# ESPBaseboard.net
KiCad netlist of a schematic drawn in EAGLE
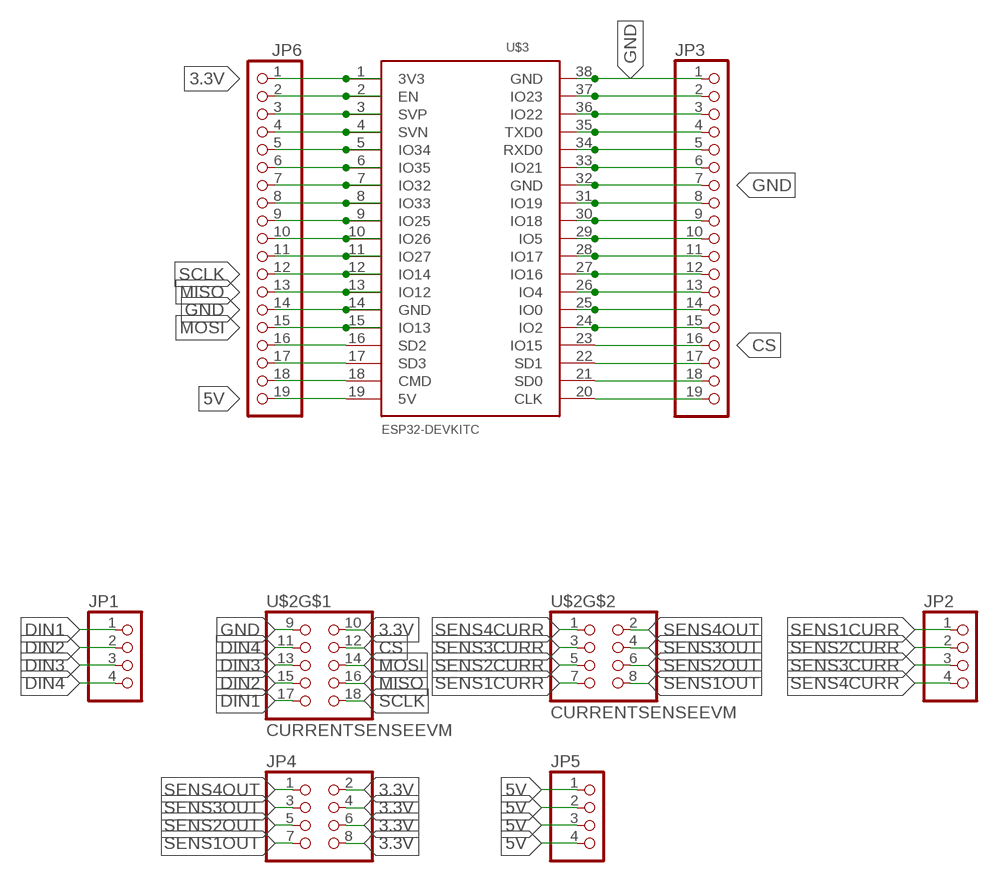
[diagram p0: schematic, sheet 1]

(export (version "E")
  (design (tool "Eeschema 10.0.6"))
  (components
    (comp (ref "JP1")
      (value "PINHD-1X4")
      (footprint "eagle-import:1X04")
      (libsource (lib "eagle-import") (part "PINHD-1X4"))
    )
    (comp (ref "JP2")
      (value "PINHD-1X4")
      (footprint "eagle-import:1X04")
      (libsource (lib "eagle-import") (part "PINHD-1X4"))
    )
    (comp (ref "JP3")
      (value "PINHD-1X19")
      (footprint "eagle-import:1X19")
      (libsource (lib "eagle-import") (part "PINHD-1X19"))
    )
    (comp (ref "JP4")
      (value "PINHD-2X4")
      (footprint "eagle-import:2X04")
      (libsource (lib "eagle-import") (part "PINHD-2X4"))
    )
    (comp (ref "JP5")
      (value "PINHD-1X4")
      (footprint "eagle-import:1X04")
      (libsource (lib "eagle-import") (part "PINHD-1X4"))
    )
    (comp (ref "JP6")
      (value "PINHD-1X19")
      (footprint "eagle-import:1X19")
      (libsource (lib "eagle-import") (part "PINHD-1X19"))
    )
    (comp (ref "U$2")
      (value "CURRENTSENSEEVM")
      (footprint "eagle-import:CURRENTSENSEEVM")
      (libsource (lib "eagle-import") (part "CURRENTSENSEEVM"))
    )
    (comp (ref "U$3")
      (value "ESP32DEVKITC")
      (footprint "eagle-import:ESP32-DEVKITC")
      (libsource (lib "eagle-import") (part "ESP32DEVKITC"))
    )
  )
  (nets
    (net (code "1") (name "3.3V") (class "Default")
      (node (ref "JP4") (pin "2") (pinfunction "2_2") (pintype "passive"))
      (node (ref "JP4") (pin "4") (pinfunction "4_4") (pintype "passive"))
      (node (ref "JP4") (pin "6") (pinfunction "6_6") (pintype "passive"))
      (node (ref "JP4") (pin "8") (pinfunction "8_8") (pintype "passive"))
      (node (ref "JP6") (pin "1") (pinfunction "1_1") (pintype "passive"))
      (node (ref "U$2") (pin "10") (pinfunction "2_10") (pintype "passive"))
      (node (ref "U$3") (pin "1") (pinfunction "3V3_1") (pintype "bidirectional"))
    )
    (net (code "2") (name "5V") (class "Default")
      (node (ref "JP5") (pin "1") (pinfunction "1_1") (pintype "passive"))
      (node (ref "JP5") (pin "2") (pinfunction "2_2") (pintype "passive"))
      (node (ref "JP5") (pin "3") (pinfunction "3_3") (pintype "passive"))
      (node (ref "JP5") (pin "4") (pinfunction "4_4") (pintype "passive"))
      (node (ref "JP6") (pin "19") (pinfunction "19_19") (pintype "passive"))
      (node (ref "U$3") (pin "19") (pinfunction "5V_19") (pintype "bidirectional"))
    )
    (net (code "3") (name "CS") (class "Default")
      (node (ref "JP3") (pin "10") (pinfunction "10_10") (pintype "passive"))
      (node (ref "JP3") (pin "16") (pinfunction "16_16") (pintype "passive"))
      (node (ref "U$2") (pin "12") (pinfunction "4_12") (pintype "passive"))
      (node (ref "U$3") (pin "23") (pinfunction "IO15_23") (pintype "bidirectional"))
      (node (ref "U$3") (pin "29") (pinfunction "IO5_29") (pintype "bidirectional"))
    )
    (net (code "4") (name "DIN1") (class "Default")
      (node (ref "JP1") (pin "1") (pinfunction "1_1") (pintype "passive"))
      (node (ref "U$2") (pin "17") (pinfunction "9_17") (pintype "passive"))
    )
    (net (code "5") (name "DIN2") (class "Default")
      (node (ref "JP1") (pin "2") (pinfunction "2_2") (pintype "passive"))
      (node (ref "U$2") (pin "15") (pinfunction "7_15") (pintype "passive"))
    )
    (net (code "6") (name "DIN3") (class "Default")
      (node (ref "JP1") (pin "3") (pinfunction "3_3") (pintype "passive"))
      (node (ref "U$2") (pin "13") (pinfunction "5_13") (pintype "passive"))
    )
    (net (code "7") (name "DIN4") (class "Default")
      (node (ref "JP1") (pin "4") (pinfunction "4_4") (pintype "passive"))
      (node (ref "U$2") (pin "11") (pinfunction "3_11") (pintype "passive"))
    )
    (net (code "8") (name "GND") (class "Default")
      (node (ref "JP3") (pin "1") (pinfunction "1_1") (pintype "passive"))
      (node (ref "JP3") (pin "7") (pinfunction "7_7") (pintype "passive"))
      (node (ref "JP6") (pin "14") (pinfunction "14_14") (pintype "passive"))
      (node (ref "U$2") (pin "9") (pinfunction "1_9") (pintype "passive"))
      (node (ref "U$3") (pin "14") (pinfunction "GND_14") (pintype "bidirectional"))
      (node (ref "U$3") (pin "32") (pinfunction "GND_32") (pintype "bidirectional"))
      (node (ref "U$3") (pin "38") (pinfunction "GND_38") (pintype "bidirectional"))
    )
    (net (code "9") (name "MISO") (class "Default")
      (node (ref "JP3") (pin "8") (pinfunction "8_8") (pintype "passive"))
      (node (ref "JP6") (pin "13") (pinfunction "13_13") (pintype "passive"))
      (node (ref "U$2") (pin "16") (pinfunction "8_16") (pintype "passive"))
      (node (ref "U$3") (pin "13") (pinfunction "IO12_13") (pintype "bidirectional"))
      (node (ref "U$3") (pin "31") (pinfunction "IO19_31") (pintype "bidirectional"))
    )
    (net (code "10") (name "MOSI") (class "Default")
      (node (ref "JP3") (pin "2") (pinfunction "2_2") (pintype "passive"))
      (node (ref "JP6") (pin "15") (pinfunction "15_15") (pintype "passive"))
      (node (ref "U$2") (pin "14") (pinfunction "6_14") (pintype "passive"))
      (node (ref "U$3") (pin "15") (pinfunction "IO13_15") (pintype "bidirectional"))
      (node (ref "U$3") (pin "37") (pinfunction "IO23_37") (pintype "bidirectional"))
    )
    (net (code "11") (name "Net-(U$3-CLK)") (class "Default")
      (node (ref "JP3") (pin "19") (pinfunction "19_19") (pintype "passive"))
      (node (ref "U$3") (pin "20") (pinfunction "CLK_20") (pintype "bidirectional"))
    )
    (net (code "12") (name "Net-(U$3-CMD)") (class "Default")
      (node (ref "JP6") (pin "18") (pinfunction "18_18") (pintype "passive"))
      (node (ref "U$3") (pin "18") (pinfunction "CMD_18") (pintype "bidirectional"))
    )
    (net (code "13") (name "Net-(U$3-EN)") (class "Default")
      (node (ref "JP6") (pin "2") (pinfunction "2_2") (pintype "passive"))
      (node (ref "U$3") (pin "2") (pinfunction "EN_2") (pintype "bidirectional"))
    )
    (net (code "14") (name "Net-(U$3-IO0)") (class "Default")
      (node (ref "JP3") (pin "14") (pinfunction "14_14") (pintype "passive"))
      (node (ref "U$3") (pin "25") (pinfunction "IO0_25") (pintype "bidirectional"))
    )
    (net (code "15") (name "Net-(U$3-IO2)") (class "Default")
      (node (ref "JP3") (pin "15") (pinfunction "15_15") (pintype "passive"))
      (node (ref "U$3") (pin "24") (pinfunction "IO2_24") (pintype "bidirectional"))
    )
    (net (code "16") (name "Net-(U$3-IO4)") (class "Default")
      (node (ref "JP3") (pin "13") (pinfunction "13_13") (pintype "passive"))
      (node (ref "U$3") (pin "26") (pinfunction "IO4_26") (pintype "bidirectional"))
    )
    (net (code "17") (name "Net-(U$3-IO16)") (class "Default")
      (node (ref "JP3") (pin "12") (pinfunction "12_12") (pintype "passive"))
      (node (ref "U$3") (pin "27") (pinfunction "IO16_27") (pintype "bidirectional"))
    )
    (net (code "18") (name "Net-(U$3-IO17)") (class "Default")
      (node (ref "JP3") (pin "11") (pinfunction "11_11") (pintype "passive"))
      (node (ref "U$3") (pin "28") (pinfunction "IO17_28") (pintype "bidirectional"))
    )
    (net (code "19") (name "Net-(U$3-IO21)") (class "Default")
      (node (ref "JP3") (pin "6") (pinfunction "6_6") (pintype "passive"))
      (node (ref "U$3") (pin "33") (pinfunction "IO21_33") (pintype "bidirectional"))
    )
    (net (code "20") (name "Net-(U$3-IO22)") (class "Default")
      (node (ref "JP3") (pin "3") (pinfunction "3_3") (pintype "passive"))
      (node (ref "U$3") (pin "36") (pinfunction "IO22_36") (pintype "bidirectional"))
    )
    (net (code "21") (name "Net-(U$3-IO25)") (class "Default")
      (node (ref "JP6") (pin "9") (pinfunction "9_9") (pintype "passive"))
      (node (ref "U$3") (pin "9") (pinfunction "IO25_9") (pintype "bidirectional"))
    )
    (net (code "22") (name "Net-(U$3-IO26)") (class "Default")
      (node (ref "JP6") (pin "10") (pinfunction "10_10") (pintype "passive"))
      (node (ref "U$3") (pin "10") (pinfunction "IO26_10") (pintype "bidirectional"))
    )
    (net (code "23") (name "Net-(U$3-IO27)") (class "Default")
      (node (ref "JP6") (pin "11") (pinfunction "11_11") (pintype "passive"))
      (node (ref "U$3") (pin "11") (pinfunction "IO27_11") (pintype "bidirectional"))
    )
    (net (code "24") (name "Net-(U$3-IO32)") (class "Default")
      (node (ref "JP6") (pin "7") (pinfunction "7_7") (pintype "passive"))
      (node (ref "U$3") (pin "7") (pinfunction "IO32_7") (pintype "bidirectional"))
    )
    (net (code "25") (name "Net-(U$3-IO33)") (class "Default")
      (node (ref "JP6") (pin "8") (pinfunction "8_8") (pintype "passive"))
      (node (ref "U$3") (pin "8") (pinfunction "IO33_8") (pintype "bidirectional"))
    )
    (net (code "26") (name "Net-(U$3-IO34)") (class "Default")
      (node (ref "JP6") (pin "5") (pinfunction "5_5") (pintype "passive"))
      (node (ref "U$3") (pin "5") (pinfunction "IO34_5") (pintype "bidirectional"))
    )
    (net (code "27") (name "Net-(U$3-RXD0)") (class "Default")
      (node (ref "JP3") (pin "5") (pinfunction "5_5") (pintype "passive"))
      (node (ref "U$3") (pin "34") (pinfunction "RXD0_34") (pintype "bidirectional"))
    )
    (net (code "28") (name "Net-(U$3-SD0)") (class "Default")
      (node (ref "JP3") (pin "18") (pinfunction "18_18") (pintype "passive"))
      (node (ref "U$3") (pin "21") (pinfunction "SD0_21") (pintype "bidirectional"))
    )
    (net (code "29") (name "Net-(U$3-SD1)") (class "Default")
      (node (ref "JP3") (pin "17") (pinfunction "17_17") (pintype "passive"))
      (node (ref "U$3") (pin "22") (pinfunction "SD1_22") (pintype "bidirectional"))
    )
    (net (code "30") (name "Net-(U$3-SD2)") (class "Default")
      (node (ref "JP6") (pin "16") (pinfunction "16_16") (pintype "passive"))
      (node (ref "U$3") (pin "16") (pinfunction "SD2_16") (pintype "bidirectional"))
    )
    (net (code "31") (name "Net-(U$3-SD3)") (class "Default")
      (node (ref "JP6") (pin "17") (pinfunction "17_17") (pintype "passive"))
      (node (ref "U$3") (pin "17") (pinfunction "SD3_17") (pintype "bidirectional"))
    )
    (net (code "32") (name "Net-(U$3-SVN)") (class "Default")
      (node (ref "JP6") (pin "4") (pinfunction "4_4") (pintype "passive"))
      (node (ref "U$3") (pin "4") (pinfunction "SVN_4") (pintype "bidirectional"))
    )
    (net (code "33") (name "Net-(U$3-SVP)") (class "Default")
      (node (ref "JP6") (pin "3") (pinfunction "3_3") (pintype "passive"))
      (node (ref "U$3") (pin "3") (pinfunction "SVP_3") (pintype "bidirectional"))
    )
    (net (code "34") (name "Net-(U$3-TXD0)") (class "Default")
      (node (ref "JP3") (pin "4") (pinfunction "4_4") (pintype "passive"))
      (node (ref "U$3") (pin "35") (pinfunction "TXD0_35") (pintype "bidirectional"))
    )
    (net (code "35") (name "SCLK") (class "Default")
      (node (ref "JP3") (pin "9") (pinfunction "9_9") (pintype "passive"))
      (node (ref "JP6") (pin "12") (pinfunction "12_12") (pintype "passive"))
      (node (ref "JP6") (pin "6") (pinfunction "6_6") (pintype "passive"))
      (node (ref "U$2") (pin "18") (pinfunction "10_18") (pintype "passive"))
      (node (ref "U$3") (pin "12") (pinfunction "IO14_12") (pintype "bidirectional"))
      (node (ref "U$3") (pin "30") (pinfunction "IO18_30") (pintype "bidirectional"))
      (node (ref "U$3") (pin "6") (pinfunction "IO35_6") (pintype "bidirectional"))
    )
    (net (code "36") (name "SENS1CURR") (class "Default")
      (node (ref "JP2") (pin "1") (pinfunction "1_1") (pintype "passive"))
      (node (ref "U$2") (pin "7") (pinfunction "7_7") (pintype "passive"))
    )
    (net (code "37") (name "SENS1OUT") (class "Default")
      (node (ref "JP4") (pin "7") (pinfunction "7_7") (pintype "passive"))
      (node (ref "U$2") (pin "8") (pinfunction "8_8") (pintype "passive"))
    )
    (net (code "38") (name "SENS2CURR") (class "Default")
      (node (ref "JP2") (pin "2") (pinfunction "2_2") (pintype "passive"))
      (node (ref "U$2") (pin "5") (pinfunction "5_5") (pintype "passive"))
    )
    (net (code "39") (name "SENS2OUT") (class "Default")
      (node (ref "JP4") (pin "5") (pinfunction "5_5") (pintype "passive"))
      (node (ref "U$2") (pin "6") (pinfunction "6_6") (pintype "passive"))
    )
    (net (code "40") (name "SENS3CURR") (class "Default")
      (node (ref "JP2") (pin "3") (pinfunction "3_3") (pintype "passive"))
      (node (ref "U$2") (pin "3") (pinfunction "3_3") (pintype "passive"))
    )
    (net (code "41") (name "SENS3OUT") (class "Default")
      (node (ref "JP4") (pin "3") (pinfunction "3_3") (pintype "passive"))
      (node (ref "U$2") (pin "4") (pinfunction "4_4") (pintype "passive"))
    )
    (net (code "42") (name "SENS4CURR") (class "Default")
      (node (ref "JP2") (pin "4") (pinfunction "4_4") (pintype "passive"))
      (node (ref "U$2") (pin "1") (pinfunction "1_1") (pintype "passive"))
    )
    (net (code "43") (name "SENS4OUT") (class "Default")
      (node (ref "JP4") (pin "1") (pinfunction "1_1") (pintype "passive"))
      (node (ref "U$2") (pin "2") (pinfunction "2_2") (pintype "passive"))
    )
  )
)
